# fonte12v.net
KiCad netlist of a schematic drawn in EAGLE
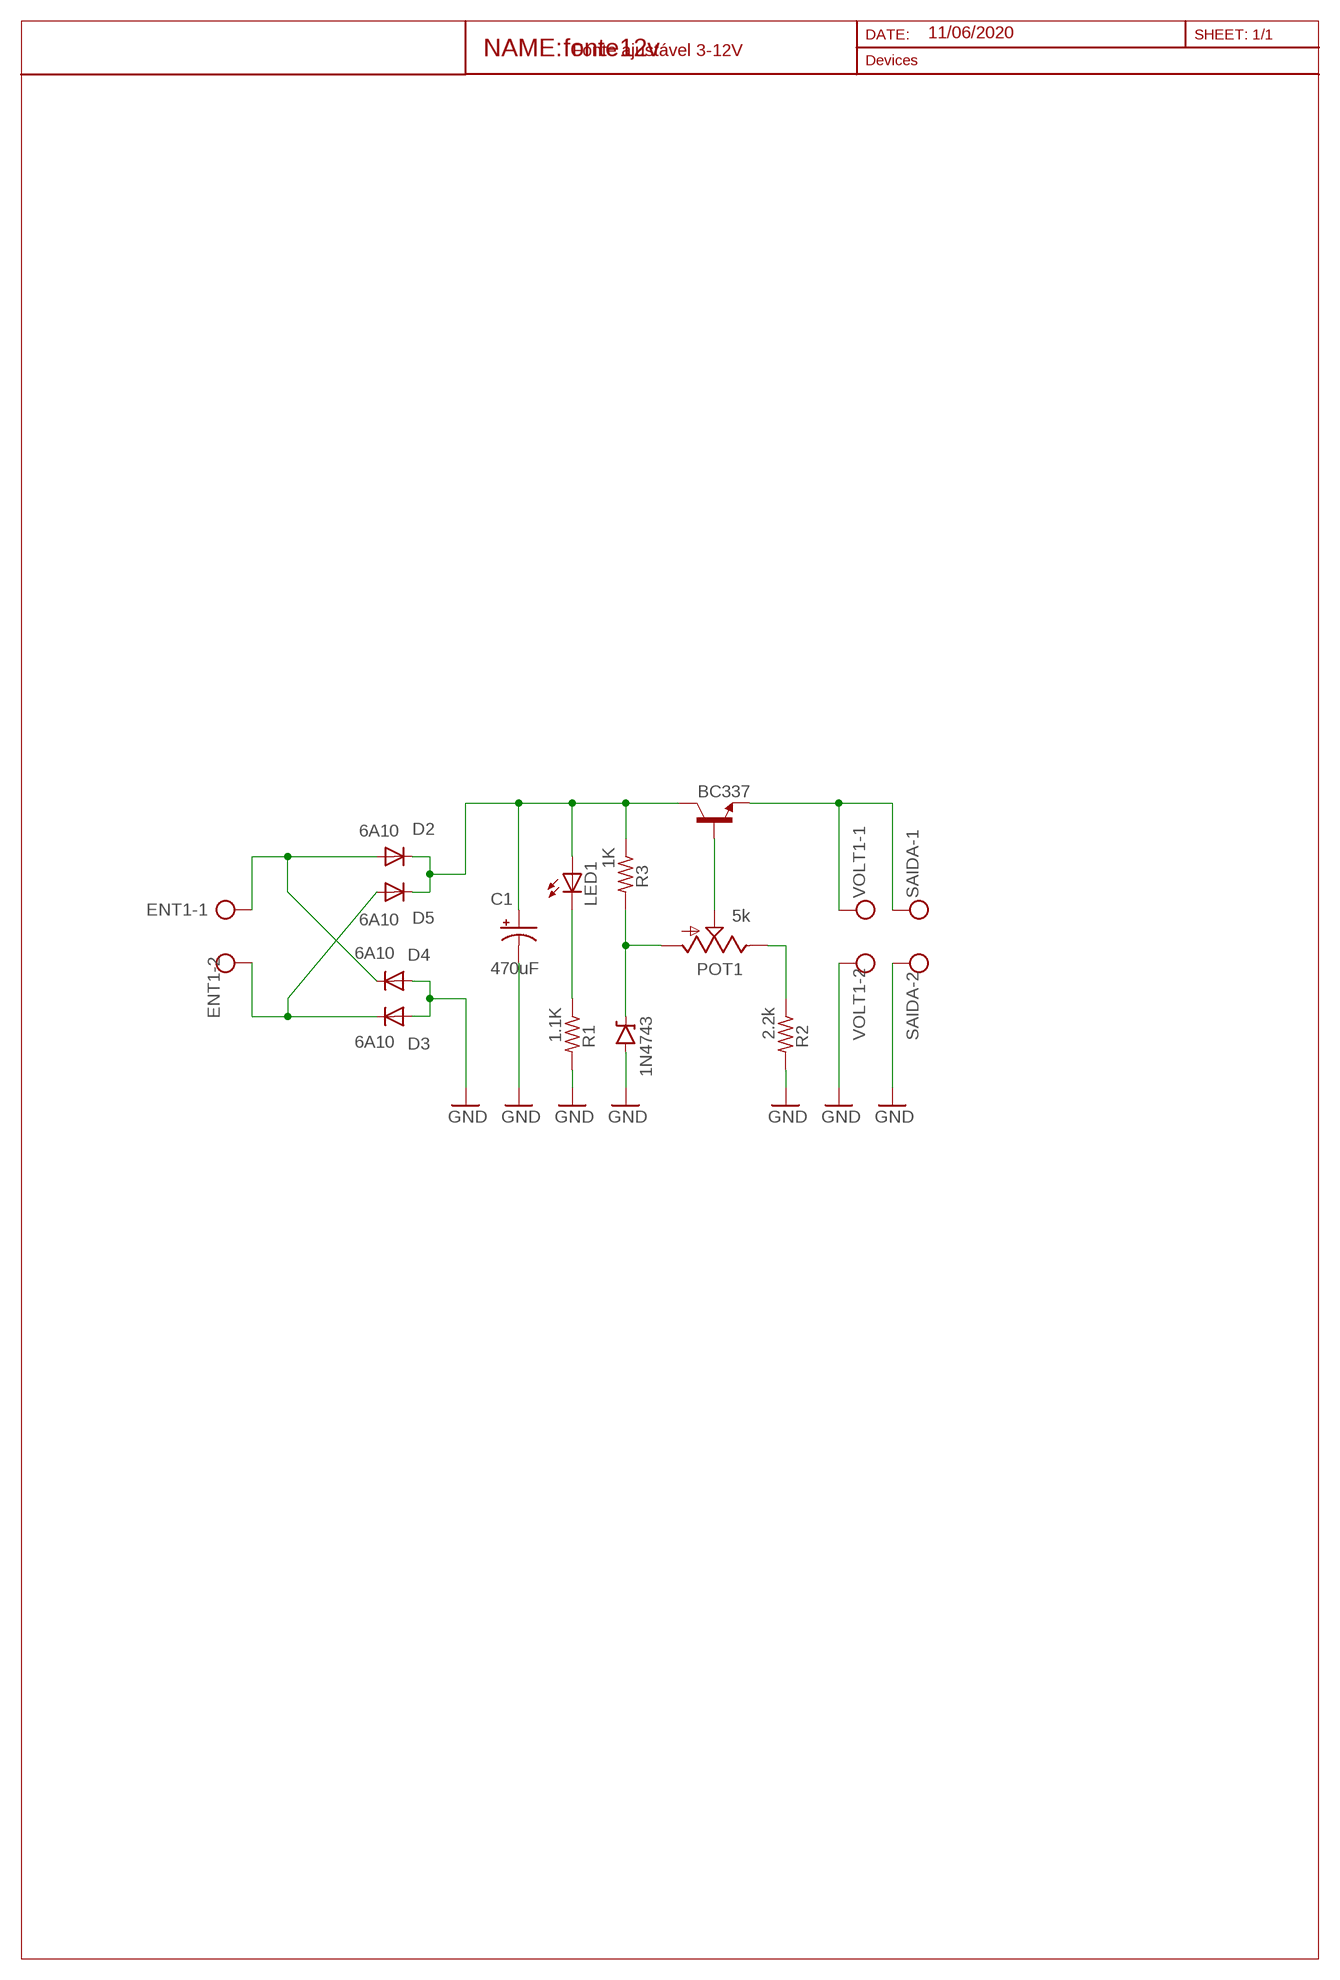
[diagram p0: schematic, sheet 1]

(export (version "E")
  (design (tool "Eeschema 10.0.6"))
  (components
    (comp (ref "1N4743")
      (value "BZT52")
      (footprint "eagle-import:DIODE-BZT52")
      (libsource (lib "eagle-import") (part "DIODE-ZENER"))
    )
    (comp (ref "C1")
      (value "470uF")
      (footprint "eagle-import:E5-13")
      (libsource (lib "eagle-import") (part "CPOL-USE5-13"))
    )
    (comp (ref "D2")
      (value "6A10")
      (footprint "eagle-import:DO41-10")
      (libsource (lib "eagle-import") (part "1N4004"))
    )
    (comp (ref "D3")
      (value "6A10")
      (footprint "eagle-import:DO41-10")
      (libsource (lib "eagle-import") (part "1N4004"))
    )
    (comp (ref "D4")
      (value "6A10")
      (footprint "eagle-import:DO41-10")
      (libsource (lib "eagle-import") (part "1N4004"))
    )
    (comp (ref "D5")
      (value "6A10")
      (footprint "eagle-import:DO41-10")
      (libsource (lib "eagle-import") (part "1N4004"))
    )
    (comp (ref "ENT1")
      (value "AK500/2-H")
      (footprint "eagle-import:AK500_2-H")
      (libsource (lib "eagle-import") (part "AK500/2-H"))
    )
    (comp (ref "LED1")
      (value "LED5MM")
      (footprint "eagle-import:LED5MM")
      (libsource (lib "eagle-import") (part "LED5MM"))
    )
    (comp (ref "POT1")
      (value "5k")
      (footprint "eagle-import:ALPS_POT")
      (libsource (lib "eagle-import") (part "POT"))
    )
    (comp (ref "R1")
      (value "1.1K")
      (footprint "eagle-import:0805-THM")
      (libsource (lib "eagle-import") (part "FLIPFLOP-RES"))
    )
    (comp (ref "R2")
      (value "2.2k")
      (footprint "eagle-import:0805-THM")
      (libsource (lib "eagle-import") (part "FLIPFLOP-RES"))
    )
    (comp (ref "R3")
      (value "1K")
      (footprint "eagle-import:0805-THM")
      (libsource (lib "eagle-import") (part "FLIPFLOP-RES"))
    )
    (comp (ref "SAIDA")
      (value "AK500/2-H")
      (footprint "eagle-import:AK500_2-H")
      (libsource (lib "eagle-import") (part "AK500/2-H"))
    )
    (comp (ref "T1")
      (value "BC337")
      (footprint "eagle-import:TO92")
      (libsource (lib "eagle-import") (part "BC337"))
    )
    (comp (ref "VOLT1")
      (value "AK500/2-H")
      (footprint "eagle-import:AK500_2-H")
      (libsource (lib "eagle-import") (part "AK500/2-H"))
    )
  )
  (nets
    (net (code "1") (name "GND") (class "Default")
      (node (ref "1N4743") (pin "A") (pinfunction "A_A") (pintype "passive"))
      (node (ref "C1") (pin "-") (pinfunction "-_-") (pintype "passive"))
      (node (ref "D3") (pin "A") (pinfunction "A_A") (pintype "passive"))
      (node (ref "D4") (pin "A") (pinfunction "A_A") (pintype "passive"))
      (node (ref "R1") (pin "2") (pinfunction "2_2") (pintype "passive"))
      (node (ref "R2") (pin "2") (pinfunction "2_2") (pintype "passive"))
      (node (ref "SAIDA") (pin "2") (pinfunction "KL_2") (pintype "passive"))
      (node (ref "VOLT1") (pin "2") (pinfunction "KL_2") (pintype "passive"))
    )
    (net (code "2") (name "Net-(ENT1A-KL)") (class "Default")
      (node (ref "D2") (pin "A") (pinfunction "A_A") (pintype "passive"))
      (node (ref "D4") (pin "C") (pinfunction "C_C") (pintype "passive"))
      (node (ref "ENT1") (pin "1") (pinfunction "KL_1") (pintype "passive"))
    )
    (net (code "3") (name "Net-(ENT1B-KL)") (class "Default")
      (node (ref "D3") (pin "C") (pinfunction "C_C") (pintype "passive"))
      (node (ref "D5") (pin "A") (pinfunction "A_A") (pintype "passive"))
      (node (ref "ENT1") (pin "2") (pinfunction "KL_2") (pintype "passive"))
    )
    (net (code "4") (name "Net-(LED1-C)") (class "Default")
      (node (ref "LED1") (pin "K") (pinfunction "C_K") (pintype "passive"))
      (node (ref "R1") (pin "1") (pinfunction "1_1") (pintype "passive"))
    )
    (net (code "5") (name "Net-(POT1-A)") (class "Default")
      (node (ref "1N4743") (pin "C") (pinfunction "C_C") (pintype "passive"))
      (node (ref "POT1") (pin "P$3") (pinfunction "A_P$3") (pintype "passive"))
      (node (ref "R3") (pin "2") (pinfunction "2_2") (pintype "passive"))
    )
    (net (code "6") (name "Net-(POT1-E)") (class "Default")
      (node (ref "POT1") (pin "P$1") (pinfunction "E_P$1") (pintype "passive"))
      (node (ref "R2") (pin "1") (pinfunction "1_1") (pintype "passive"))
    )
    (net (code "7") (name "Net-(POT1-S)") (class "Default")
      (node (ref "POT1") (pin "P$2") (pinfunction "S_P$2") (pintype "passive"))
      (node (ref "T1") (pin "2") (pinfunction "B_2") (pintype "passive"))
    )
    (net (code "8") (name "Net-(SAIDAA-KL)") (class "Default")
      (node (ref "SAIDA") (pin "1") (pinfunction "KL_1") (pintype "passive"))
      (node (ref "T1") (pin "1") (pinfunction "E_1") (pintype "passive"))
      (node (ref "VOLT1") (pin "1") (pinfunction "KL_1") (pintype "passive"))
    )
    (net (code "9") (name "Net-(T1-C)") (class "Default")
      (node (ref "C1") (pin "+") (pinfunction "+_+") (pintype "passive"))
      (node (ref "D2") (pin "C") (pinfunction "C_C") (pintype "passive"))
      (node (ref "D5") (pin "C") (pinfunction "C_C") (pintype "passive"))
      (node (ref "LED1") (pin "A") (pinfunction "A_A") (pintype "passive"))
      (node (ref "R3") (pin "1") (pinfunction "1_1") (pintype "passive"))
      (node (ref "T1") (pin "3") (pinfunction "C_3") (pintype "passive"))
    )
  )
)
